# EE209_Schematic.net
KiCad netlist of a schematic drawn in Altium Designer
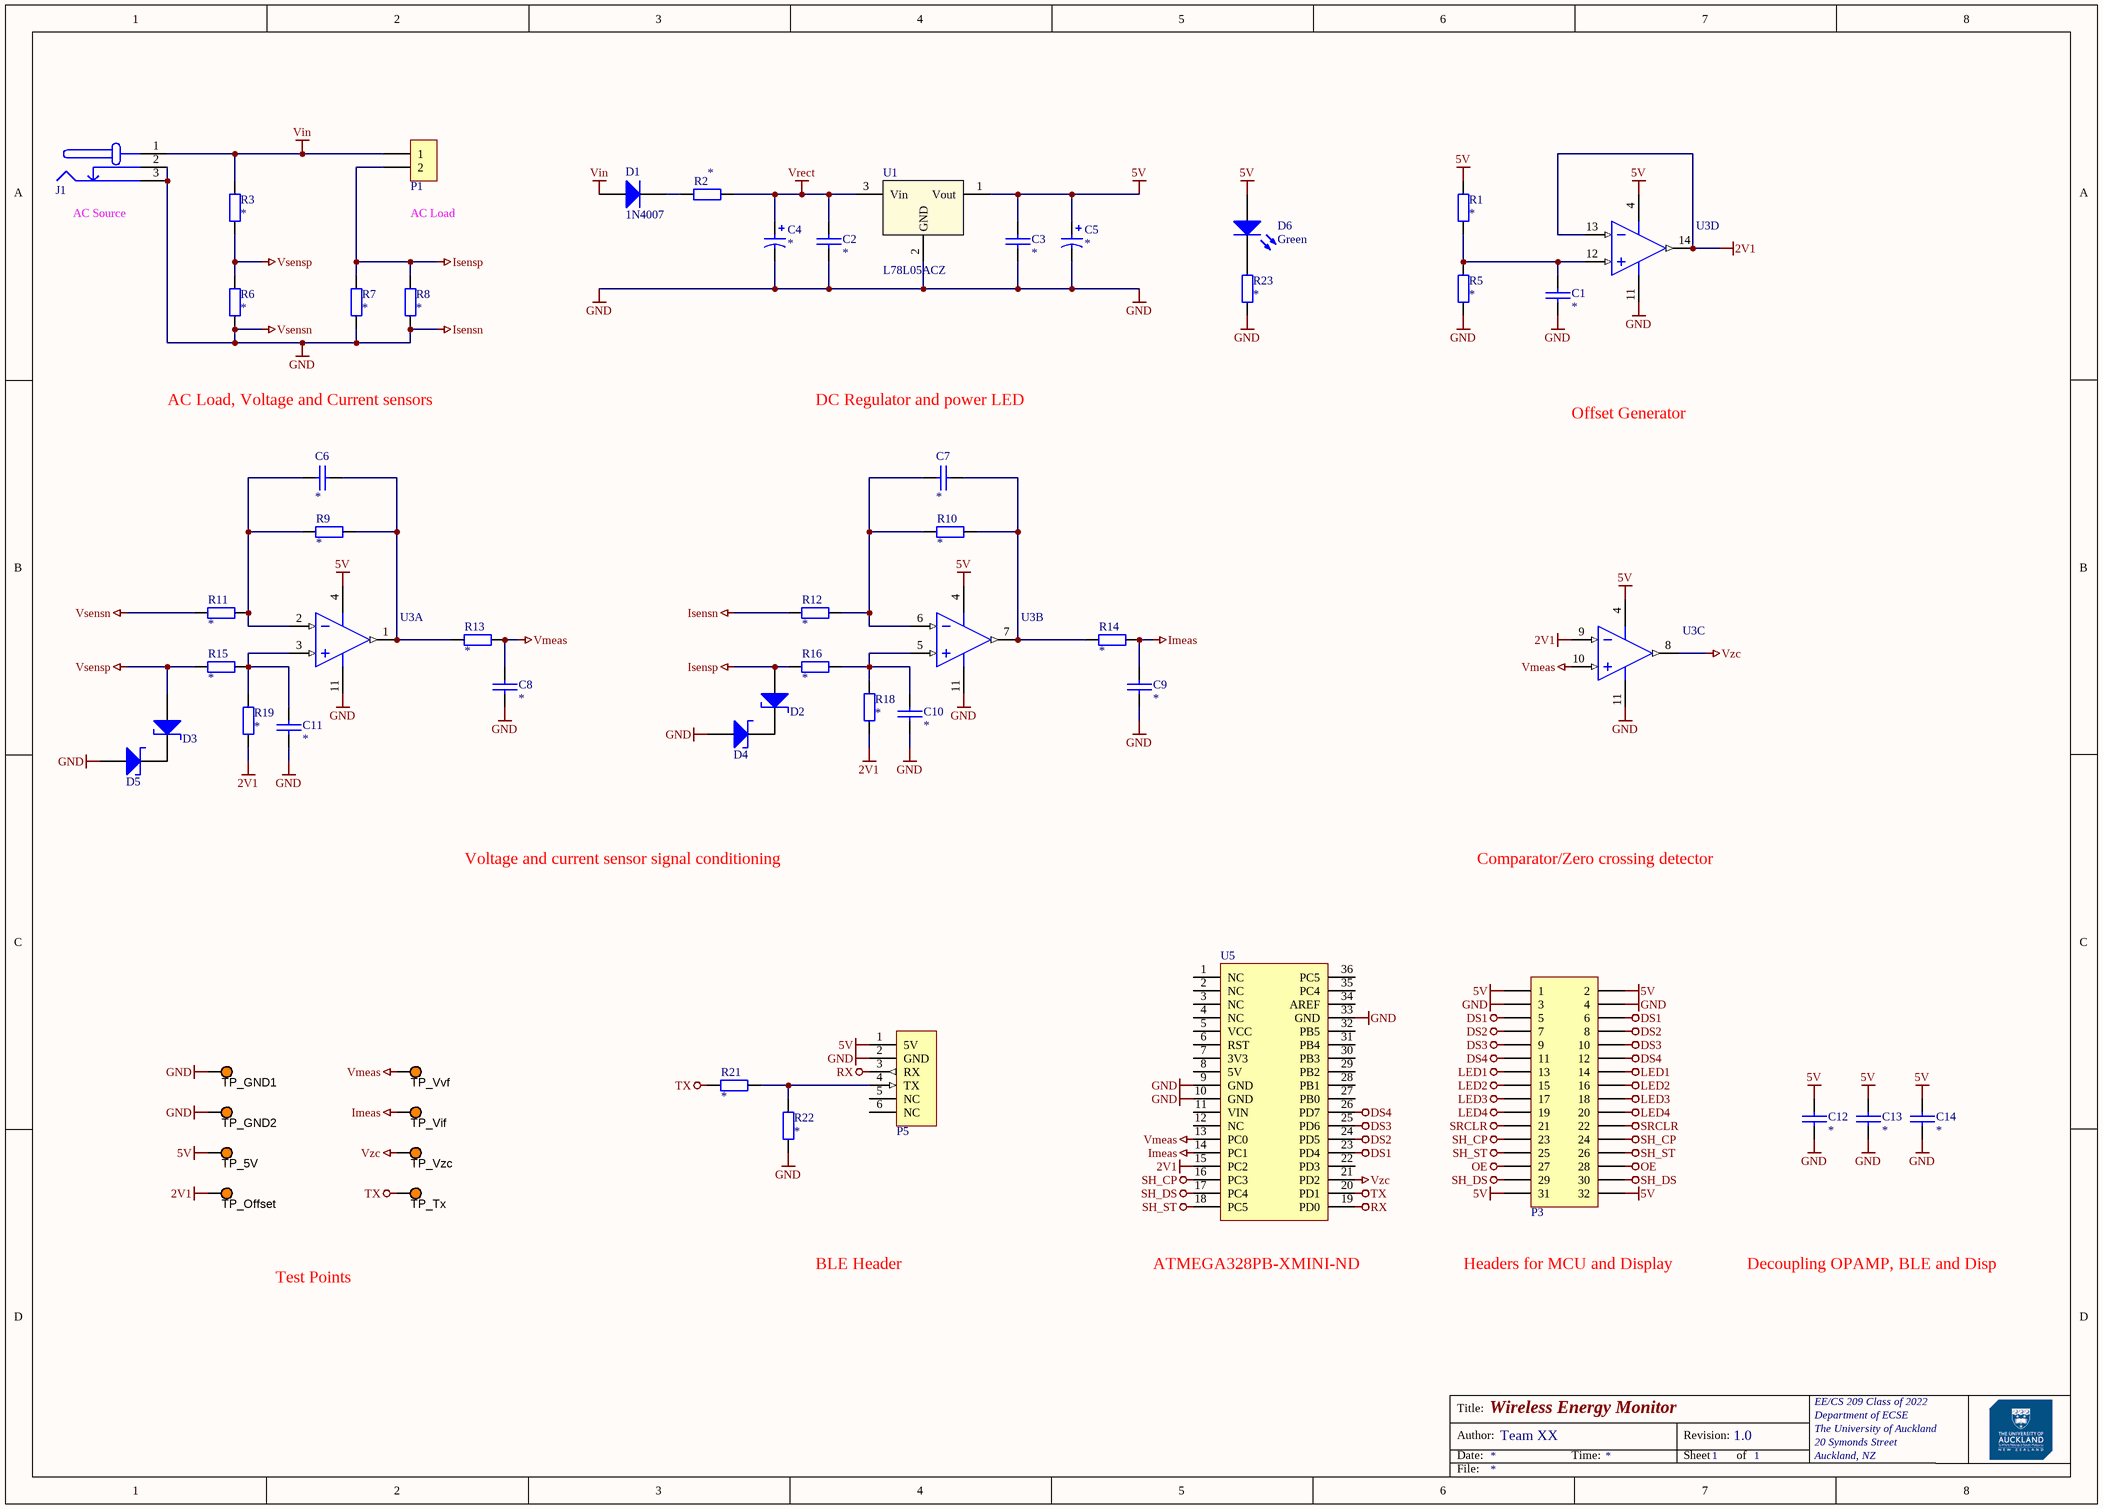
[diagram p0: EE209_Schematic.SchDoc]

(export (version "E")
  (design (tool "Eeschema 10.0.6"))
  (components
    (comp (ref "C1")
      (value "*")
      (footprint "CCAP-5P0")
      (description "TH ceramic capacitor with 5mm pitch")
      (libsource (lib "EE209_Library") (part "CerCap_TH_5P0"))
    )
    (comp (ref "C2")
      (value "*")
      (footprint "CCAP-5P0")
      (description "TH ceramic capacitor with 5mm pitch")
      (libsource (lib "EE209_Library") (part "CerCap_TH_5P0"))
    )
    (comp (ref "C3")
      (value "*")
      (footprint "CCAP-5P0")
      (description "TH ceramic capacitor with 5mm pitch")
      (libsource (lib "EE209_Library") (part "CerCap_TH_5P0"))
    )
    (comp (ref "C4")
      (value "*")
      (footprint "CAP-RAD-2.5mm Pitch")
      (description "Electrolytic capacitor with radial package, 2mm pitch and 5.2mm diameter")
      (fields (field (name "PUBLISHER") "Altium Limited"))
      (libsource (lib "EE209_Library") (part "ElecCap_TH_2P0"))
    )
    (comp (ref "C5")
      (value "*")
      (footprint "CAP-RAD-2.5mm Pitch")
      (description "Electrolytic capacitor with radial package, 2mm pitch and 5.2mm diameter")
      (fields (field (name "PUBLISHER") "Altium Limited"))
      (libsource (lib "EE209_Library") (part "ElecCap_TH_2P0"))
    )
    (comp (ref "C6")
      (value "*")
      (footprint "CCAP-5P0")
      (description "TH ceramic capacitor with 5mm pitch")
      (libsource (lib "EE209_Library") (part "CerCap_TH_5P0"))
    )
    (comp (ref "C7")
      (value "*")
      (footprint "CCAP-5P0")
      (description "TH ceramic capacitor with 5mm pitch")
      (libsource (lib "EE209_Library") (part "CerCap_TH_5P0"))
    )
    (comp (ref "C8")
      (value "*")
      (footprint "CCAP-5P0")
      (description "TH ceramic capacitor with 5mm pitch")
      (libsource (lib "EE209_Library") (part "CerCap_TH_5P0"))
    )
    (comp (ref "C9")
      (value "*")
      (footprint "CCAP-5P0")
      (description "TH ceramic capacitor with 5mm pitch")
      (libsource (lib "EE209_Library") (part "CerCap_TH_5P0"))
    )
    (comp (ref "C10")
      (value "*")
      (footprint "CCAP-5P0")
      (description "TH ceramic capacitor with 5mm pitch")
      (libsource (lib "EE209_Library") (part "CerCap_TH_5P0"))
    )
    (comp (ref "C11")
      (value "*")
      (footprint "CCAP-5P0")
      (description "TH ceramic capacitor with 5mm pitch")
      (libsource (lib "EE209_Library") (part "CerCap_TH_5P0"))
    )
    (comp (ref "C12")
      (value "*")
      (footprint "CCAP-5P0")
      (description "TH ceramic capacitor with 5mm pitch")
      (libsource (lib "EE209_Library") (part "CerCap_TH_5P0"))
    )
    (comp (ref "C13")
      (value "*")
      (footprint "CCAP-5P0")
      (description "TH ceramic capacitor with 5mm pitch")
      (libsource (lib "EE209_Library") (part "CerCap_TH_5P0"))
    )
    (comp (ref "C14")
      (value "*")
      (footprint "CCAP-5P0")
      (description "TH ceramic capacitor with 5mm pitch")
      (libsource (lib "EE209_Library") (part "CerCap_TH_5P0"))
    )
    (comp (ref "D1")
      (value "1N4007")
      (footprint "1N4007-MFG")
      (description "1N4007 1000V standard axial diode")
      (libsource (lib "EE209_Library") (part "1N4007_TH_4AX0"))
    )
    (comp (ref "D2")
      (value "BZX79-CXVX")
      (footprint "AXIAL-Zener-0.4")
      (description "Axial zener diode BZX79 series")
      (fields
        (field (name "MANUFACTURER") "Nexperia USA Inc.")
        (field (name "MANUFACTURER PART NUMBER") "BZX79-C4V7,143")
      )
      (libsource (lib "EE209_Library") (part "Zener_TH_4AX0"))
    )
    (comp (ref "D3")
      (value "BZX79-CXVX")
      (footprint "AXIAL-Zener-0.4")
      (description "Axial zener diode BZX79 series")
      (fields
        (field (name "MANUFACTURER") "Nexperia USA Inc.")
        (field (name "MANUFACTURER PART NUMBER") "BZX79-C4V7,143")
      )
      (libsource (lib "EE209_Library") (part "Zener_TH_4AX0"))
    )
    (comp (ref "D4")
      (value "BZX79-CXVX")
      (footprint "AXIAL-Zener-0.4")
      (description "Axial zener diode BZX79 series")
      (fields
        (field (name "MANUFACTURER") "Nexperia USA Inc.")
        (field (name "MANUFACTURER PART NUMBER") "BZX79-C4V7,143")
      )
      (libsource (lib "EE209_Library") (part "Zener_TH_4AX0"))
    )
    (comp (ref "D5")
      (value "BZX79-CXVX")
      (footprint "AXIAL-Zener-0.4")
      (description "Axial zener diode BZX79 series")
      (fields
        (field (name "MANUFACTURER") "Nexperia USA Inc.")
        (field (name "MANUFACTURER PART NUMBER") "BZX79-C4V7,143")
      )
      (libsource (lib "EE209_Library") (part "Zener_TH_4AX0"))
    )
    (comp (ref "D6")
      (value "Green")
      (footprint "LED")
      (description "Typical throughole GaAs LED with 2.54mm pitch")
      (fields (field (name "MANUFACTURER") "Generic Components") (field (name "PUBLISHER") "Altium Limited"))
      (libsource (lib "EE209_Library") (part "LED_TH_2P54"))
    )
    (comp (ref "J1")
      (value "DC barrel jack")
      (footprint "AC-Socket")
      (description "DC barrel jack connection to AC source")
      (libsource (lib "EE209_Library") (part "AC_Input"))
    )
    (comp (ref "P1")
      (value "Dual Banana Plugs")
      (footprint "Dual Banana Plug")
      (description "Dual banana plugs connection to the AC load")
      (fields (field (name "PUBLISHER") "Altium Limited"))
      (libsource (lib "EE209_Library") (part "AC_Output"))
    )
    (comp (ref "P3")
      (value "Display")
      (footprint "Display")
      (description "16-Pin Header Connecting Display")
      (libsource (lib "EE209_Library") (part "Display"))
    )
    (comp (ref "P5")
      (value "BLE Module Header")
      (footprint "HM10_HDR1X6")
      (description "2.54mm pitch 6-pin header for BLE module")
      (fields (field (name "PUBLISHER") "Altium Limited"))
      (libsource (lib "EE209_Library") (part "BLEModule_TH"))
    )
    (comp (ref "R1")
      (value "*")
      (footprint "AXIAL-0.4")
      (description "Through hole resistor")
      (fields (field (name "PUBLISHER") "Altium Limited"))
      (libsource (lib "EE209_Library") (part "Res_TH_0AX4"))
    )
    (comp (ref "R2")
      (value "*")
      (footprint "AXIAL-0.4")
      (description "Through hole resistor")
      (fields (field (name "PUBLISHER") "Altium Limited"))
      (libsource (lib "") (part "Res_TH_0AX4_1"))
    )
    (comp (ref "R3")
      (value "*")
      (footprint "AXIAL-0.4")
      (description "Through hole resistor")
      (fields (field (name "PUBLISHER") "Altium Limited"))
      (libsource (lib "EE209_Library") (part "Res_TH_0AX4"))
    )
    (comp (ref "R5")
      (value "*")
      (footprint "AXIAL-0.4")
      (description "Through hole resistor")
      (fields (field (name "PUBLISHER") "Altium Limited"))
      (libsource (lib "EE209_Library") (part "Res_TH_0AX4"))
    )
    (comp (ref "R6")
      (value "*")
      (footprint "AXIAL-0.4")
      (description "Through hole resistor")
      (fields (field (name "PUBLISHER") "Altium Limited"))
      (libsource (lib "EE209_Library") (part "Res_TH_0AX4"))
    )
    (comp (ref "R7")
      (value "*")
      (footprint "AXIAL-0.4")
      (description "Through hole resistor")
      (fields (field (name "PUBLISHER") "Altium Limited"))
      (libsource (lib "EE209_Library") (part "Res_TH_0AX4"))
    )
    (comp (ref "R8")
      (value "*")
      (footprint "AXIAL-0.4")
      (description "Through hole resistor")
      (fields (field (name "PUBLISHER") "Altium Limited"))
      (libsource (lib "EE209_Library") (part "Res_TH_0AX4"))
    )
    (comp (ref "R9")
      (value "*")
      (footprint "AXIAL-0.4")
      (description "Through hole resistor")
      (fields (field (name "PUBLISHER") "Altium Limited"))
      (libsource (lib "") (part "Res_TH_0AX4_1"))
    )
    (comp (ref "R10")
      (value "*")
      (footprint "AXIAL-0.4")
      (description "Through hole resistor")
      (fields (field (name "PUBLISHER") "Altium Limited"))
      (libsource (lib "") (part "Res_TH_0AX4_2"))
    )
    (comp (ref "R11")
      (value "*")
      (footprint "AXIAL-0.4")
      (description "Through hole resistor")
      (fields (field (name "PUBLISHER") "Altium Limited"))
      (libsource (lib "") (part "Res_TH_0AX4_1"))
    )
    (comp (ref "R12")
      (value "*")
      (footprint "AXIAL-0.4")
      (description "Through hole resistor")
      (fields (field (name "PUBLISHER") "Altium Limited"))
      (libsource (lib "") (part "Res_TH_0AX4_1"))
    )
    (comp (ref "R13")
      (value "*")
      (footprint "AXIAL-0.4")
      (description "Through hole resistor")
      (fields (field (name "PUBLISHER") "Altium Limited"))
      (libsource (lib "") (part "Res_TH_0AX4_1"))
    )
    (comp (ref "R14")
      (value "*")
      (footprint "AXIAL-0.4")
      (description "Through hole resistor")
      (fields (field (name "PUBLISHER") "Altium Limited"))
      (libsource (lib "") (part "Res_TH_0AX4_1"))
    )
    (comp (ref "R15")
      (value "*")
      (footprint "AXIAL-0.4")
      (description "Through hole resistor")
      (fields (field (name "PUBLISHER") "Altium Limited"))
      (libsource (lib "") (part "Res_TH_0AX4_1"))
    )
    (comp (ref "R16")
      (value "*")
      (footprint "AXIAL-0.4")
      (description "Through hole resistor")
      (fields (field (name "PUBLISHER") "Altium Limited"))
      (libsource (lib "") (part "Res_TH_0AX4_1"))
    )
    (comp (ref "R18")
      (value "*")
      (footprint "AXIAL-0.4")
      (description "Through hole resistor")
      (fields (field (name "PUBLISHER") "Altium Limited"))
      (libsource (lib "EE209_Library") (part "Res_TH_0AX4"))
    )
    (comp (ref "R19")
      (value "*")
      (footprint "AXIAL-0.4")
      (description "Through hole resistor")
      (fields (field (name "PUBLISHER") "Altium Limited"))
      (libsource (lib "EE209_Library") (part "Res_TH_0AX4"))
    )
    (comp (ref "R21")
      (value "*")
      (footprint "AXIAL-0.4")
      (description "Through hole resistor")
      (fields (field (name "PUBLISHER") "Altium Limited"))
      (libsource (lib "") (part "Res_TH_0AX4_1"))
    )
    (comp (ref "R22")
      (value "*")
      (footprint "AXIAL-0.4")
      (description "Through hole resistor")
      (fields (field (name "PUBLISHER") "Altium Limited"))
      (libsource (lib "EE209_Library") (part "Res_TH_0AX4"))
    )
    (comp (ref "R23")
      (value "*")
      (footprint "AXIAL-0.4")
      (description "Through hole resistor")
      (fields (field (name "PUBLISHER") "Altium Limited"))
      (libsource (lib "EE209_Library") (part "Res_TH_0AX4"))
    )
    (comp (ref "TP_5V")
      (value "5003")
      (footprint "TP_TH")
      (description "Test Point, Orange, 1-Pin THD, RoHS")
      (libsource (lib "EE209_Library") (part "TestPoint"))
    )
    (comp (ref "TP_GND1")
      (value "5003")
      (footprint "TP_TH")
      (description "Test Point, Orange, 1-Pin THD, RoHS")
      (libsource (lib "EE209_Library") (part "TestPoint"))
    )
    (comp (ref "TP_GND2")
      (value "5003")
      (footprint "TP_TH")
      (description "Test Point, Orange, 1-Pin THD, RoHS")
      (libsource (lib "EE209_Library") (part "TestPoint"))
    )
    (comp (ref "TP_Offset")
      (value "5003")
      (footprint "TP_TH")
      (description "Test Point, Orange, 1-Pin THD, RoHS")
      (libsource (lib "EE209_Library") (part "TestPoint"))
    )
    (comp (ref "TP_Tx")
      (value "5003")
      (footprint "TP_TH")
      (description "Test Point, Orange, 1-Pin THD, RoHS")
      (libsource (lib "EE209_Library") (part "TestPoint"))
    )
    (comp (ref "TP_Vif")
      (value "5003")
      (footprint "TP_TH")
      (description "Test Point, Orange, 1-Pin THD, RoHS")
      (libsource (lib "EE209_Library") (part "TestPoint"))
    )
    (comp (ref "TP_Vvf")
      (value "5003")
      (footprint "TP_TH")
      (description "Test Point, Orange, 1-Pin THD, RoHS")
      (libsource (lib "EE209_Library") (part "TestPoint"))
    )
    (comp (ref "TP_Vzc")
      (value "5003")
      (footprint "TP_TH")
      (description "Test Point, Orange, 1-Pin THD, RoHS")
      (libsource (lib "EE209_Library") (part "TestPoint"))
    )
    (comp (ref "U1")
      (value "L78L05ACZ")
      (footprint "TO-92")
      (description "Voltage Regulator 5V")
      (fields
        (field (name "MANUFACTURER") "ON Semiconductor")
        (field (name "MANUFACTURER PART NUMBER") "LM78L05ACZX")
      )
      (libsource (lib "EE209_Library") (part "L78L05_TH_TO92"))
    )
    (comp (ref "U3")
      (value "LM324")
      (footprint "DIP-14")
      (description "IC OPAMP GP 14DIP")
      (fields
        (field (name "MANUFACTURER") "ON Semiconductor")
        (field (name "MANUFACTURER PART NUMBER") "LM324N")
      )
      (libsource (lib "EE209_Library") (part "LM324N_TH_DIP16"))
    )
    (comp (ref "U5")
      (value "ATmega328PB Xplained Mini Header")
      (footprint "ATmeg328P Xplained")
      (description "Dual 18-pin headers connecting to ATmega328PB Xplained Mini")
      (fields
        (field (name "MANUFACTURER") "Microchip Technology")
        (field (name "MANUFACTURER PART NUMBER") "ATMEGA328PB-XMINI")
      )
      (libsource (lib "EE209_Library") (part "ATmega328PBXplained_TH"))
    )
  )
  (nets
    (net (code "1") (name "2V1") (class "Default")
      (node (ref "R18") (pin "1") (pinfunction "1_1") (pintype "passive"))
      (node (ref "R19") (pin "1") (pinfunction "1_1") (pintype "passive"))
      (node (ref "TP_Offset") (pin "1") (pinfunction "1_1") (pintype "passive"))
      (node (ref "U3") (pin "13") (pinfunction "VIND-_13") (pintype "input"))
      (node (ref "U3") (pin "14") (pinfunction "VOUTD_14") (pintype "output"))
      (node (ref "U3") (pin "9") (pinfunction "VINC-_9") (pintype "input"))
      (node (ref "U5") (pin "15") (pinfunction "PC2_15") (pintype "passive"))
    )
    (net (code "2") (name "5V") (class "Default")
      (node (ref "C12") (pin "1") (pinfunction "1_1") (pintype "passive"))
      (node (ref "C13") (pin "1") (pinfunction "1_1") (pintype "passive"))
      (node (ref "C14") (pin "1") (pinfunction "1_1") (pintype "passive"))
      (node (ref "C3") (pin "1") (pinfunction "1_1") (pintype "passive"))
      (node (ref "C5") (pin "1") (pinfunction "1_1") (pintype "passive"))
      (node (ref "D6") (pin "1") (pinfunction "A_1") (pintype "passive"))
      (node (ref "P3") (pin "1") (pinfunction "1_1") (pintype "passive"))
      (node (ref "P3") (pin "2") (pinfunction "2_2") (pintype "passive"))
      (node (ref "P3") (pin "31") (pinfunction "31_31") (pintype "passive"))
      (node (ref "P3") (pin "32") (pinfunction "32_32") (pintype "passive"))
      (node (ref "P5") (pin "1") (pinfunction "5V_1") (pintype "passive"))
      (node (ref "R1") (pin "2") (pinfunction "2_2") (pintype "passive"))
      (node (ref "TP_5V") (pin "1") (pinfunction "1_1") (pintype "passive"))
      (node (ref "U1") (pin "1") (pinfunction "Vout_1") (pintype "passive"))
      (node (ref "U3") (pin "4") (pinfunction "VDD_4") (pintype "power_in"))
    )
    (net (code "3") (name "DS1") (class "Default")
      (node (ref "P3") (pin "5") (pinfunction "5_5") (pintype "passive"))
      (node (ref "P3") (pin "6") (pinfunction "6_6") (pintype "passive"))
      (node (ref "U5") (pin "23") (pinfunction "PD4_23") (pintype "passive"))
    )
    (net (code "4") (name "DS2") (class "Default")
      (node (ref "P3") (pin "7") (pinfunction "7_7") (pintype "passive"))
      (node (ref "P3") (pin "8") (pinfunction "8_8") (pintype "passive"))
      (node (ref "U5") (pin "24") (pinfunction "PD5_24") (pintype "passive"))
    )
    (net (code "5") (name "DS3") (class "Default")
      (node (ref "P3") (pin "10") (pinfunction "10_10") (pintype "passive"))
      (node (ref "P3") (pin "9") (pinfunction "9_9") (pintype "passive"))
      (node (ref "U5") (pin "25") (pinfunction "PD6_25") (pintype "passive"))
    )
    (net (code "6") (name "DS4") (class "Default")
      (node (ref "P3") (pin "11") (pinfunction "11_11") (pintype "passive"))
      (node (ref "P3") (pin "12") (pinfunction "12_12") (pintype "passive"))
      (node (ref "U5") (pin "26") (pinfunction "PD7_26") (pintype "passive"))
    )
    (net (code "7") (name "GND") (class "Default")
      (node (ref "C1") (pin "2") (pinfunction "2_2") (pintype "passive"))
      (node (ref "C10") (pin "2") (pinfunction "2_2") (pintype "passive"))
      (node (ref "C11") (pin "2") (pinfunction "2_2") (pintype "passive"))
      (node (ref "C12") (pin "2") (pinfunction "2_2") (pintype "passive"))
      (node (ref "C13") (pin "2") (pinfunction "2_2") (pintype "passive"))
      (node (ref "C14") (pin "2") (pinfunction "2_2") (pintype "passive"))
      (node (ref "C2") (pin "2") (pinfunction "2_2") (pintype "passive"))
      (node (ref "C3") (pin "2") (pinfunction "2_2") (pintype "passive"))
      (node (ref "C4") (pin "2") (pinfunction "2_2") (pintype "passive"))
      (node (ref "C5") (pin "2") (pinfunction "2_2") (pintype "passive"))
      (node (ref "C8") (pin "1") (pinfunction "1_1") (pintype "passive"))
      (node (ref "C9") (pin "2") (pinfunction "2_2") (pintype "passive"))
      (node (ref "D4") (pin "1") (pinfunction "A_1") (pintype "passive"))
      (node (ref "D5") (pin "1") (pinfunction "A_1") (pintype "passive"))
      (node (ref "J1") (pin "2") (pinfunction "GND_ALT_2") (pintype "power_in"))
      (node (ref "J1") (pin "3") (pinfunction "GND_3") (pintype "power_in"))
      (node (ref "P3") (pin "3") (pinfunction "3_3") (pintype "passive"))
      (node (ref "P3") (pin "4") (pinfunction "4_4") (pintype "passive"))
      (node (ref "P5") (pin "2") (pinfunction "GND_2") (pintype "passive"))
      (node (ref "R11") (pin "1") (pinfunction "1_1") (pintype "passive"))
      (node (ref "R12") (pin "1") (pinfunction "1_1") (pintype "passive"))
      (node (ref "R22") (pin "1") (pinfunction "1_1") (pintype "passive"))
      (node (ref "R23") (pin "1") (pinfunction "1_1") (pintype "passive"))
      (node (ref "R5") (pin "1") (pinfunction "1_1") (pintype "passive"))
      (node (ref "R6") (pin "1") (pinfunction "1_1") (pintype "passive"))
      (node (ref "R7") (pin "1") (pinfunction "1_1") (pintype "passive"))
      (node (ref "R8") (pin "1") (pinfunction "1_1") (pintype "passive"))
      (node (ref "TP_GND1") (pin "1") (pinfunction "1_1") (pintype "passive"))
      (node (ref "TP_GND2") (pin "1") (pinfunction "1_1") (pintype "passive"))
      (node (ref "U1") (pin "2") (pinfunction "GND_2") (pintype "passive"))
      (node (ref "U3") (pin "11") (pinfunction "VSS_11") (pintype "power_in"))
      (node (ref "U5") (pin "10") (pinfunction "GND_10") (pintype "power_in"))
      (node (ref "U5") (pin "33") (pinfunction "GND_33") (pintype "passive"))
      (node (ref "U5") (pin "9") (pinfunction "GND_9") (pintype "power_in"))
    )
    (net (code "8") (name "Imeas") (class "Default")
      (node (ref "C9") (pin "1") (pinfunction "1_1") (pintype "passive"))
      (node (ref "R14") (pin "2") (pinfunction "2_2") (pintype "passive"))
      (node (ref "TP_Vif") (pin "1") (pinfunction "1_1") (pintype "passive"))
      (node (ref "U5") (pin "14") (pinfunction "PC1_14") (pintype "passive"))
    )
    (net (code "9") (name "Isensp") (class "Default")
      (node (ref "D2") (pin "1") (pinfunction "A_1") (pintype "passive"))
      (node (ref "P1") (pin "2") (pinfunction "2_2") (pintype "passive"))
      (node (ref "R16") (pin "1") (pinfunction "1_1") (pintype "passive"))
      (node (ref "R7") (pin "2") (pinfunction "2_2") (pintype "passive"))
      (node (ref "R8") (pin "2") (pinfunction "2_2") (pintype "passive"))
    )
    (net (code "10") (name "LED1") (class "Default")
      (node (ref "P3") (pin "13") (pinfunction "13_13") (pintype "passive"))
      (node (ref "P3") (pin "14") (pinfunction "14_14") (pintype "passive"))
    )
    (net (code "11") (name "LED2") (class "Default")
      (node (ref "P3") (pin "15") (pinfunction "15_15") (pintype "passive"))
      (node (ref "P3") (pin "16") (pinfunction "16_16") (pintype "passive"))
    )
    (net (code "12") (name "LED3") (class "Default")
      (node (ref "P3") (pin "17") (pinfunction "17_17") (pintype "passive"))
      (node (ref "P3") (pin "18") (pinfunction "18_18") (pintype "passive"))
    )
    (net (code "13") (name "LED4") (class "Default")
      (node (ref "P3") (pin "19") (pinfunction "19_19") (pintype "passive"))
      (node (ref "P3") (pin "20") (pinfunction "20_20") (pintype "passive"))
    )
    (net (code "14") (name "Net-(D1-K)") (class "Default")
      (node (ref "D1") (pin "2") (pinfunction "K_2") (pintype "passive"))
      (node (ref "R2") (pin "1") (pinfunction "1_1") (pintype "passive"))
    )
    (net (code "15") (name "Net-(D2-K)") (class "Default")
      (node (ref "D2") (pin "2") (pinfunction "K_2") (pintype "passive"))
      (node (ref "D4") (pin "2") (pinfunction "K_2") (pintype "passive"))
    )
    (net (code "16") (name "Net-(D3-K)") (class "Default")
      (node (ref "D3") (pin "2") (pinfunction "K_2") (pintype "passive"))
      (node (ref "D5") (pin "2") (pinfunction "K_2") (pintype "passive"))
    )
    (net (code "17") (name "Net-(D6-K)") (class "Default")
      (node (ref "D6") (pin "2") (pinfunction "K_2") (pintype "passive"))
      (node (ref "R23") (pin "2") (pinfunction "2_2") (pintype "passive"))
    )
    (net (code "18") (name "Net-(P5-TX)") (class "Default")
      (node (ref "P5") (pin "4") (pinfunction "TX_4") (pintype "input"))
      (node (ref "R21") (pin "2") (pinfunction "2_2") (pintype "passive"))
      (node (ref "R22") (pin "2") (pinfunction "2_2") (pintype "passive"))
    )
    (net (code "19") (name "Net-(U3A-VINA+)") (class "Default")
      (node (ref "C11") (pin "1") (pinfunction "1_1") (pintype "passive"))
      (node (ref "R15") (pin "2") (pinfunction "2_2") (pintype "passive"))
      (node (ref "R19") (pin "2") (pinfunction "2_2") (pintype "passive"))
      (node (ref "U3") (pin "3") (pinfunction "VINA+_3") (pintype "input"))
    )
    (net (code "20") (name "Net-(U3A-VINA-)") (class "Default")
      (node (ref "C6") (pin "1") (pinfunction "1_1") (pintype "passive"))
      (node (ref "R11") (pin "2") (pinfunction "2_2") (pintype "passive"))
      (node (ref "R9") (pin "1") (pinfunction "1_1") (pintype "passive"))
      (node (ref "U3") (pin "2") (pinfunction "VINA-_2") (pintype "input"))
    )
    (net (code "21") (name "Net-(U3A-VOUTA)") (class "Default")
      (node (ref "C6") (pin "2") (pinfunction "2_2") (pintype "passive"))
      (node (ref "R13") (pin "1") (pinfunction "1_1") (pintype "passive"))
      (node (ref "R9") (pin "2") (pinfunction "2_2") (pintype "passive"))
      (node (ref "U3") (pin "1") (pinfunction "VOUTA_1") (pintype "output"))
    )
    (net (code "22") (name "Net-(U3B-VINB+)") (class "Default")
      (node (ref "C10") (pin "1") (pinfunction "1_1") (pintype "passive"))
      (node (ref "R16") (pin "2") (pinfunction "2_2") (pintype "passive"))
      (node (ref "R18") (pin "2") (pinfunction "2_2") (pintype "passive"))
      (node (ref "U3") (pin "5") (pinfunction "VINB+_5") (pintype "input"))
    )
    (net (code "23") (name "Net-(U3B-VINB-)") (class "Default")
      (node (ref "C7") (pin "1") (pinfunction "1_1") (pintype "passive"))
      (node (ref "R10") (pin "2") (pinfunction "2_2") (pintype "passive"))
      (node (ref "R12") (pin "2") (pinfunction "2_2") (pintype "passive"))
      (node (ref "U3") (pin "6") (pinfunction "VINB-_6") (pintype "input"))
    )
    (net (code "24") (name "Net-(U3B-VOUTB)") (class "Default")
      (node (ref "C7") (pin "2") (pinfunction "2_2") (pintype "passive"))
      (node (ref "R10") (pin "1") (pinfunction "1_1") (pintype "passive"))
      (node (ref "R14") (pin "1") (pinfunction "1_1") (pintype "passive"))
      (node (ref "U3") (pin "7") (pinfunction "VOUTB_7") (pintype "output"))
    )
    (net (code "25") (name "Net-(U3D-VIND+)") (class "Default")
      (node (ref "C1") (pin "1") (pinfunction "1_1") (pintype "passive"))
      (node (ref "R1") (pin "1") (pinfunction "1_1") (pintype "passive"))
      (node (ref "R5") (pin "2") (pinfunction "2_2") (pintype "passive"))
      (node (ref "U3") (pin "12") (pinfunction "VIND+_12") (pintype "input"))
    )
    (net (code "26") (name "OE") (class "Default")
      (node (ref "P3") (pin "27") (pinfunction "27_27") (pintype "passive"))
      (node (ref "P3") (pin "28") (pinfunction "28_28") (pintype "passive"))
    )
    (net (code "27") (name "RX") (class "Default")
      (node (ref "P5") (pin "3") (pinfunction "RX_3") (pintype "output"))
      (node (ref "U5") (pin "19") (pinfunction "PD0_19") (pintype "passive"))
    )
    (net (code "28") (name "SH_CP") (class "Default")
      (node (ref "P3") (pin "23") (pinfunction "23_23") (pintype "passive"))
      (node (ref "P3") (pin "24") (pinfunction "24_24") (pintype "passive"))
      (node (ref "U5") (pin "16") (pinfunction "PC3_16") (pintype "passive"))
    )
    (net (code "29") (name "SH_DS") (class "Default")
      (node (ref "P3") (pin "29") (pinfunction "29_29") (pintype "passive"))
      (node (ref "P3") (pin "30") (pinfunction "30_30") (pintype "passive"))
      (node (ref "U5") (pin "17") (pinfunction "PC4_17") (pintype "passive"))
    )
    (net (code "30") (name "SH_ST") (class "Default")
      (node (ref "P3") (pin "25") (pinfunction "25_25") (pintype "passive"))
      (node (ref "P3") (pin "26") (pinfunction "26_26") (pintype "passive"))
      (node (ref "U5") (pin "18") (pinfunction "PC5_18") (pintype "passive"))
    )
    (net (code "31") (name "SRCLR") (class "Default")
      (node (ref "P3") (pin "21") (pinfunction "21_21") (pintype "passive"))
      (node (ref "P3") (pin "22") (pinfunction "22_22") (pintype "passive"))
    )
    (net (code "32") (name "TX") (class "Default")
      (node (ref "R21") (pin "1") (pinfunction "1_1") (pintype "passive"))
      (node (ref "TP_Tx") (pin "1") (pinfunction "1_1") (pintype "passive"))
      (node (ref "U5") (pin "20") (pinfunction "PD1_20") (pintype "passive"))
    )
    (net (code "33") (name "Vin") (class "Default")
      (node (ref "D1") (pin "1") (pinfunction "A_1") (pintype "passive"))
      (node (ref "J1") (pin "1") (pinfunction "VCC_1") (pintype "power_in"))
      (node (ref "P1") (pin "1") (pinfunction "1_1") (pintype "passive"))
      (node (ref "R3") (pin "2") (pinfunction "2_2") (pintype "passive"))
    )
    (net (code "34") (name "Vmeas") (class "Default")
      (node (ref "C8") (pin "2") (pinfunction "2_2") (pintype "passive"))
      (node (ref "R13") (pin "2") (pinfunction "2_2") (pintype "passive"))
      (node (ref "TP_Vvf") (pin "1") (pinfunction "1_1") (pintype "passive"))
      (node (ref "U3") (pin "10") (pinfunction "VINC+_10") (pintype "input"))
      (node (ref "U5") (pin "13") (pinfunction "PC0_13") (pintype "passive"))
    )
    (net (code "35") (name "Vrect") (class "Default")
      (node (ref "C2") (pin "1") (pinfunction "1_1") (pintype "passive"))
      (node (ref "C4") (pin "1") (pinfunction "1_1") (pintype "passive"))
      (node (ref "R2") (pin "2") (pinfunction "2_2") (pintype "passive"))
      (node (ref "U1") (pin "3") (pinfunction "Vin_3") (pintype "passive"))
    )
    (net (code "36") (name "Vsensp") (class "Default")
      (node (ref "D3") (pin "1") (pinfunction "A_1") (pintype "passive"))
      (node (ref "R15") (pin "1") (pinfunction "1_1") (pintype "passive"))
      (node (ref "R3") (pin "1") (pinfunction "1_1") (pintype "passive"))
      (node (ref "R6") (pin "2") (pinfunction "2_2") (pintype "passive"))
    )
    (net (code "37") (name "Vzc") (class "Default")
      (node (ref "TP_Vzc") (pin "1") (pinfunction "1_1") (pintype "passive"))
      (node (ref "U3") (pin "8") (pinfunction "VOUTC_8") (pintype "output"))
      (node (ref "U5") (pin "21") (pinfunction "PD2_21") (pintype "passive"))
    )
    (net (code "38") (name "unconnected-(P5-NC-Pad5)") (class "Default")
      (node (ref "P5") (pin "5") (pinfunction "NC_5") (pintype "passive"))
    )
    (net (code "39") (name "unconnected-(P5-NC-Pad6)") (class "Default")
      (node (ref "P5") (pin "6") (pinfunction "NC_6") (pintype "passive"))
    )
    (net (code "40") (name "unconnected-(U5-3V3-Pad7)") (class "Default")
      (node (ref "U5") (pin "7") (pinfunction "3V3_7") (pintype "passive"))
    )
    (net (code "41") (name "unconnected-(U5-5V-Pad8)") (class "Default")
      (node (ref "U5") (pin "8") (pinfunction "5V_8") (pintype "power_in"))
    )
    (net (code "42") (name "unconnected-(U5-AREF-Pad34)") (class "Default")
      (node (ref "U5") (pin "34") (pinfunction "AREF_34") (pintype "passive"))
    )
    (net (code "43") (name "unconnected-(U5-NC-Pad1)") (class "Default")
      (node (ref "U5") (pin "1") (pinfunction "NC_1") (pintype "passive"))
    )
    (net (code "44") (name "unconnected-(U5-NC-Pad2)") (class "Default")
      (node (ref "U5") (pin "2") (pinfunction "NC_2") (pintype "passive"))
    )
    (net (code "45") (name "unconnected-(U5-NC-Pad3)") (class "Default")
      (node (ref "U5") (pin "3") (pinfunction "NC_3") (pintype "passive"))
    )
    (net (code "46") (name "unconnected-(U5-NC-Pad4)") (class "Default")
      (node (ref "U5") (pin "4") (pinfunction "NC_4") (pintype "passive"))
    )
    (net (code "47") (name "unconnected-(U5-NC-Pad12)") (class "Default")
      (node (ref "U5") (pin "12") (pinfunction "NC_12") (pintype "passive"))
    )
    (net (code "48") (name "unconnected-(U5-PB0-Pad27)") (class "Default")
      (node (ref "U5") (pin "27") (pinfunction "PB0_27") (pintype "passive"))
    )
    (net (code "49") (name "unconnected-(U5-PB1-Pad28)") (class "Default")
      (node (ref "U5") (pin "28") (pinfunction "PB1_28") (pintype "passive"))
    )
    (net (code "50") (name "unconnected-(U5-PB2-Pad29)") (class "Default")
      (node (ref "U5") (pin "29") (pinfunction "PB2_29") (pintype "passive"))
    )
    (net (code "51") (name "unconnected-(U5-PB3-Pad30)") (class "Default")
      (node (ref "U5") (pin "30") (pinfunction "PB3_30") (pintype "passive"))
    )
    (net (code "52") (name "unconnected-(U5-PB4-Pad31)") (class "Default")
      (node (ref "U5") (pin "31") (pinfunction "PB4_31") (pintype "passive"))
    )
    (net (code "53") (name "unconnected-(U5-PB5-Pad32)") (class "Default")
      (node (ref "U5") (pin "32") (pinfunction "PB5_32") (pintype "passive"))
    )
    (net (code "54") (name "unconnected-(U5-PC4-Pad35)") (class "Default")
      (node (ref "U5") (pin "35") (pinfunction "PC4_35") (pintype "passive"))
    )
    (net (code "55") (name "unconnected-(U5-PC5-Pad36)") (class "Default")
      (node (ref "U5") (pin "36") (pinfunction "PC5_36") (pintype "passive"))
    )
    (net (code "56") (name "unconnected-(U5-PD3-Pad22)") (class "Default")
      (node (ref "U5") (pin "22") (pinfunction "PD3_22") (pintype "passive"))
    )
    (net (code "57") (name "unconnected-(U5-RST-Pad6)") (class "Default")
      (node (ref "U5") (pin "6") (pinfunction "RST_6") (pintype "passive"))
    )
    (net (code "58") (name "unconnected-(U5-VCC-Pad5)") (class "Default")
      (node (ref "U5") (pin "5") (pinfunction "VCC_5") (pintype "power_in"))
    )
    (net (code "59") (name "unconnected-(U5-VIN-Pad11)") (class "Default")
      (node (ref "U5") (pin "11") (pinfunction "VIN_11") (pintype "power_in"))
    )
  )
)
